# 03-ETHERNET.net
KiCad netlist of a schematic drawn in Altium Designer
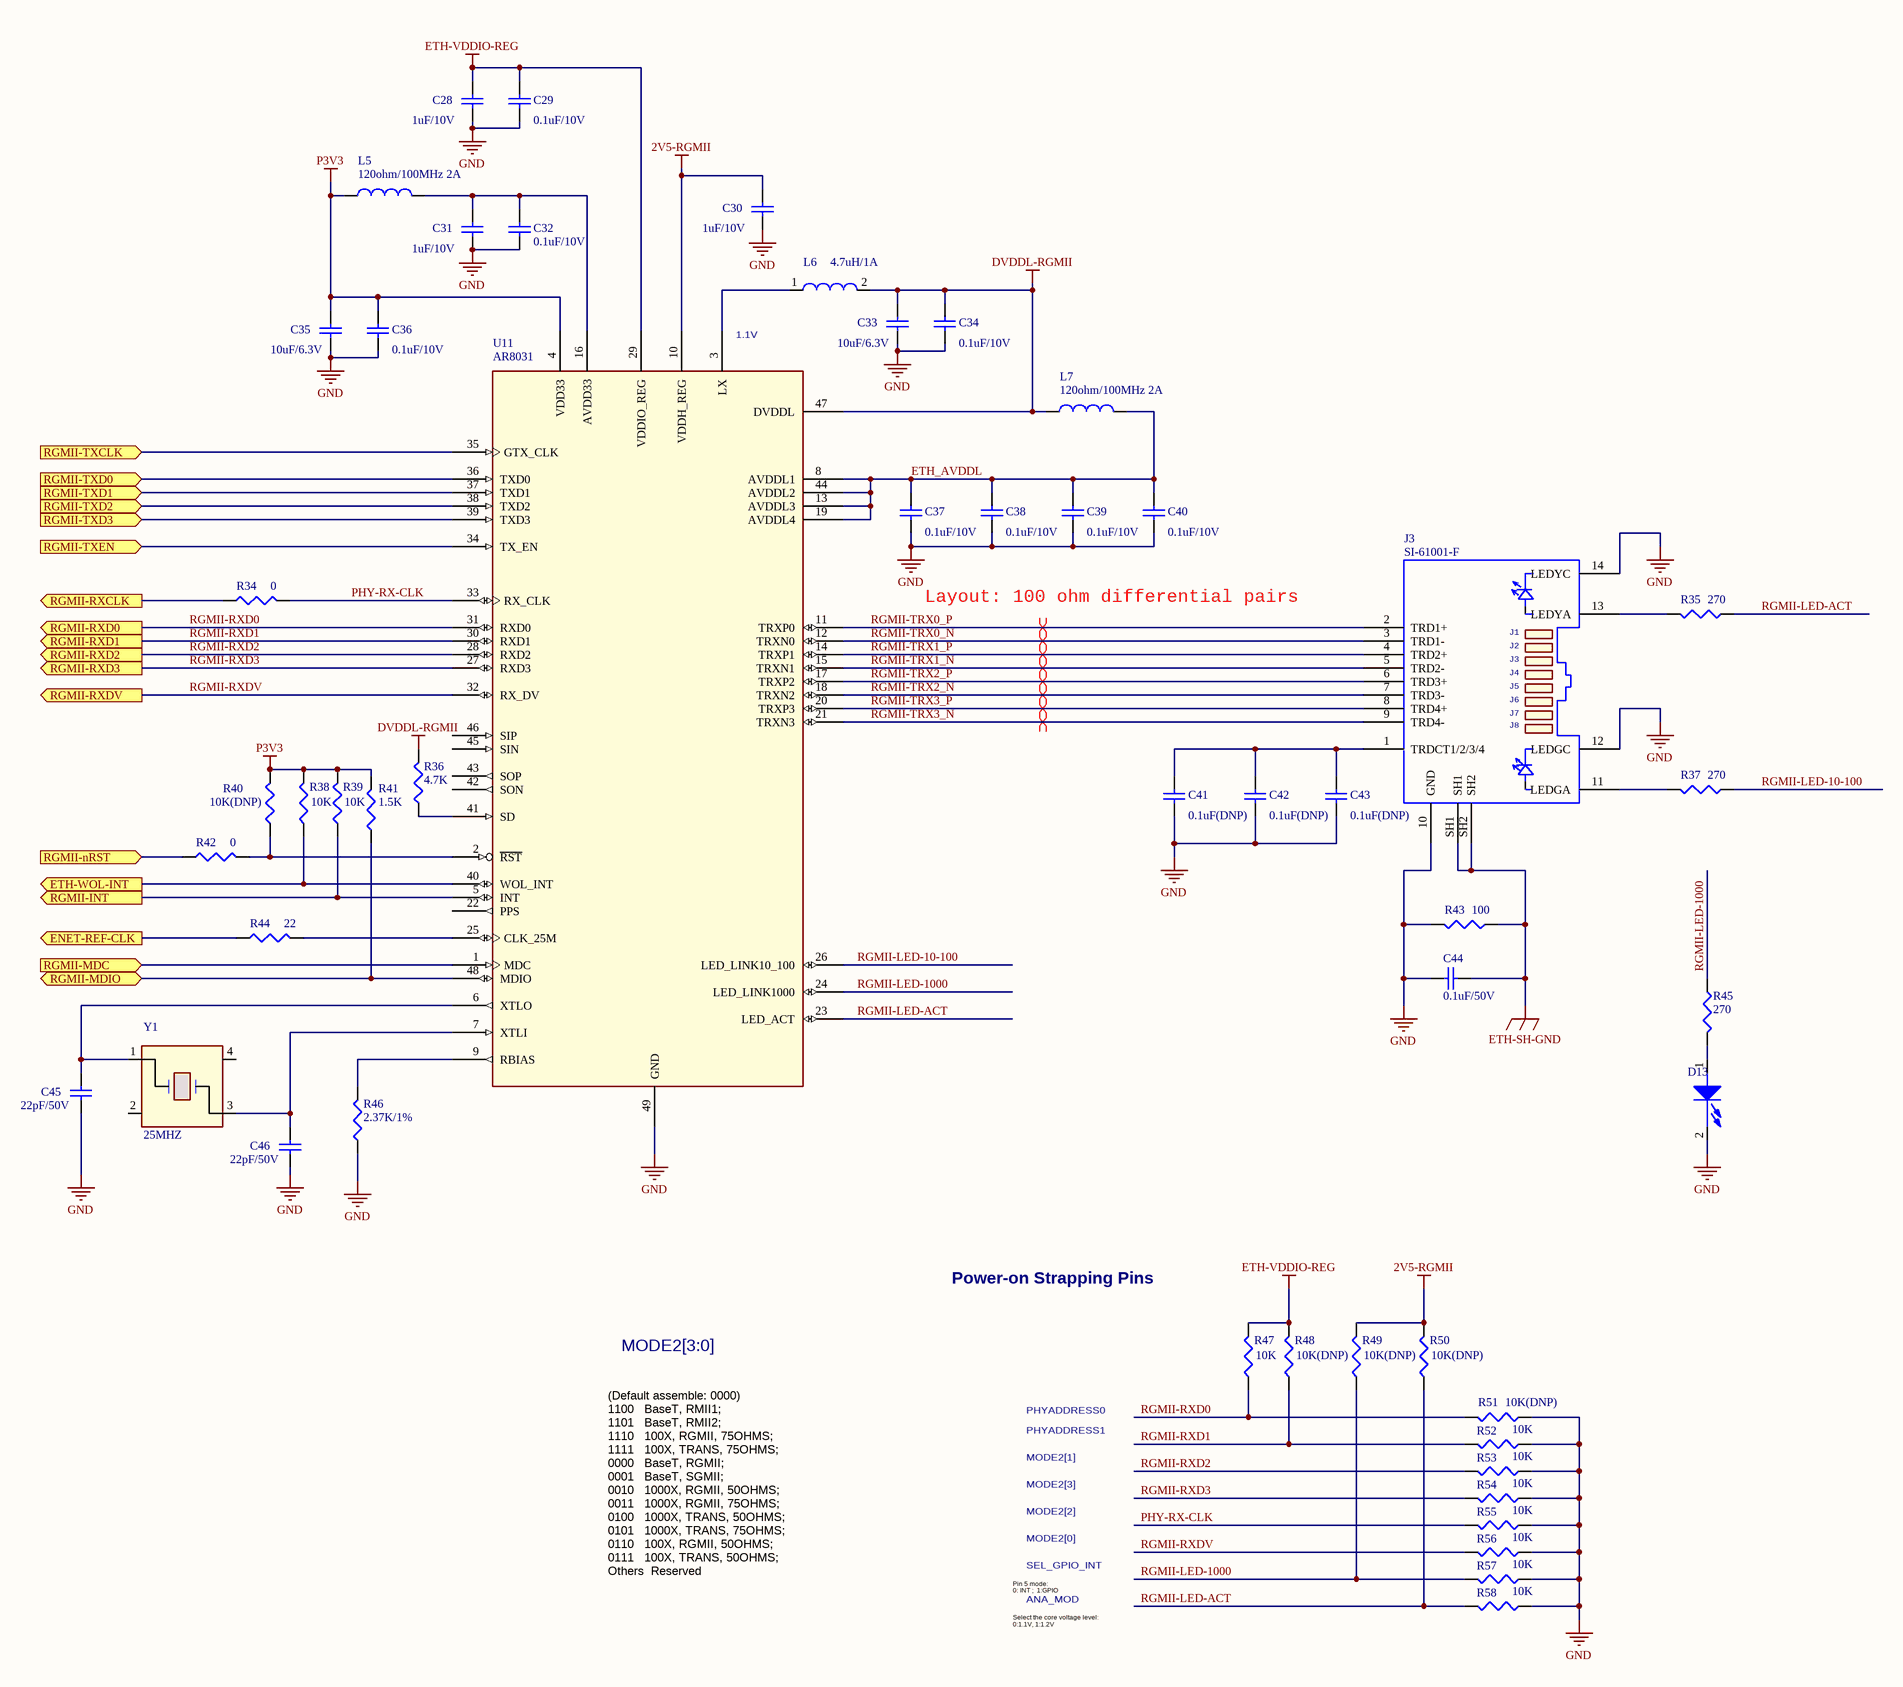
[diagram p0: 03-ETHERNET.SchDoc]

(export (version "E")
  (design (tool "Eeschema 10.0.6"))
  (components
    (comp (ref "C28")
      (value "1uF/10V")
      (footprint "0402")
      (description "Capacitor")
      (fields (field (name "PUBLISHER") "Altium Limited"))
      (libsource (lib "Miscellaneous Devices") (part "Cap"))
    )
    (comp (ref "C29")
      (value "0.1uF/10V")
      (footprint "0402")
      (description "Capacitor")
      (fields (field (name "PUBLISHER") "Altium Limited"))
      (libsource (lib "Miscellaneous Devices") (part "Cap"))
    )
    (comp (ref "C30")
      (value "1uF/10V")
      (footprint "0402")
      (description "Capacitor")
      (fields (field (name "PUBLISHER") "Altium Limited"))
      (libsource (lib "Miscellaneous Devices") (part "Cap"))
    )
    (comp (ref "C31")
      (value "1uF/10V")
      (footprint "0402")
      (description "Capacitor")
      (fields (field (name "PUBLISHER") "Altium Limited"))
      (libsource (lib "Miscellaneous Devices") (part "Cap"))
    )
    (comp (ref "C32")
      (value "0.1uF/10V")
      (footprint "0402")
      (description "Capacitor")
      (fields (field (name "PUBLISHER") "Altium Limited"))
      (libsource (lib "Miscellaneous Devices") (part "Cap"))
    )
    (comp (ref "C33")
      (value "10uF/6.3V")
      (footprint "0805")
      (description "Capacitor")
      (fields (field (name "PUBLISHER") "Altium Limited"))
      (libsource (lib "Miscellaneous Devices") (part "Cap"))
    )
    (comp (ref "C34")
      (value "0.1uF/10V")
      (footprint "0402")
      (description "Capacitor")
      (fields (field (name "PUBLISHER") "Altium Limited"))
      (libsource (lib "Miscellaneous Devices") (part "Cap"))
    )
    (comp (ref "C35")
      (value "10uF/6.3V")
      (footprint "0805")
      (description "Capacitor")
      (fields (field (name "PUBLISHER") "Altium Limited"))
      (libsource (lib "Miscellaneous Devices") (part "Cap"))
    )
    (comp (ref "C36")
      (value "0.1uF/10V")
      (footprint "0402")
      (description "Capacitor")
      (fields (field (name "PUBLISHER") "Altium Limited"))
      (libsource (lib "Miscellaneous Devices") (part "Cap"))
    )
    (comp (ref "C37")
      (value "0.1uF/10V")
      (footprint "0402")
      (description "Capacitor")
      (fields (field (name "PUBLISHER") "Altium Limited"))
      (libsource (lib "Miscellaneous Devices") (part "Cap"))
    )
    (comp (ref "C38")
      (value "0.1uF/10V")
      (footprint "0402")
      (description "Capacitor")
      (fields (field (name "PUBLISHER") "Altium Limited"))
      (libsource (lib "Miscellaneous Devices") (part "Cap"))
    )
    (comp (ref "C39")
      (value "0.1uF/10V")
      (footprint "0402")
      (description "Capacitor")
      (fields (field (name "PUBLISHER") "Altium Limited"))
      (libsource (lib "Miscellaneous Devices") (part "Cap"))
    )
    (comp (ref "C40")
      (value "0.1uF/10V")
      (footprint "0402")
      (description "Capacitor")
      (fields (field (name "PUBLISHER") "Altium Limited"))
      (libsource (lib "Miscellaneous Devices") (part "Cap"))
    )
    (comp (ref "C41")
      (value "0.1uF(DNP)")
      (footprint "0603")
      (description "Capacitor")
      (fields (field (name "PUBLISHER") "Altium Limited"))
      (libsource (lib "Miscellaneous Devices") (part "Cap"))
    )
    (comp (ref "C42")
      (value "0.1uF(DNP)")
      (footprint "0603")
      (description "Capacitor")
      (fields (field (name "PUBLISHER") "Altium Limited"))
      (libsource (lib "Miscellaneous Devices") (part "Cap"))
    )
    (comp (ref "C43")
      (value "0.1uF(DNP)")
      (footprint "0603")
      (description "Capacitor")
      (fields (field (name "PUBLISHER") "Altium Limited"))
      (libsource (lib "Miscellaneous Devices") (part "Cap"))
    )
    (comp (ref "C44")
      (value "0.1uF/50V")
      (footprint "0603")
      (description "Capacitor")
      (fields (field (name "PUBLISHER") "Altium Limited"))
      (libsource (lib "Miscellaneous Devices") (part "Cap"))
    )
    (comp (ref "C45")
      (value "22pF/50V")
      (footprint "0402")
      (description "Capacitor")
      (fields (field (name "PUBLISHER") "Altium Limited"))
      (libsource (lib "Miscellaneous Devices") (part "Cap"))
    )
    (comp (ref "C46")
      (value "22pF/50V")
      (footprint "0402")
      (description "Capacitor")
      (fields (field (name "PUBLISHER") "Altium Limited"))
      (libsource (lib "Miscellaneous Devices") (part "Cap"))
    )
    (comp (ref "D13") (value "LED GREEN") (footprint "LED0603") (libsource (lib "*") (part "LN01401_1")))
    (comp (ref "J3")
      (value "SI-61001-F")
      (footprint "SI-61001")
      (libsource (lib "Schlib") (part "SI-61001-F"))
    )
    (comp (ref "L5")
      (value "120ohm/100MHz 2A")
      (footprint "0603")
      (description "Inductor")
      (fields (field (name "PUBLISHER") "Altium Limited"))
      (libsource (lib "Miscellaneous Devices") (part "Inductor"))
    )
    (comp (ref "L6")
      (value "4.7uH/1A")
      (footprint "IND-4.7UH-1A")
      (description "IND PWR 4.7UH@1MHZ 1A 20% SMD")
      (fields (field (name "TOLERANCE") "20%"))
      (libsource (lib "*") (part "INDUCTOR"))
    )
    (comp (ref "L7")
      (value "120ohm/100MHz 2A")
      (footprint "0603")
      (description "Inductor")
      (fields (field (name "PUBLISHER") "Altium Limited"))
      (libsource (lib "Miscellaneous Devices") (part "Inductor"))
    )
    (comp (ref "R34") (value "0") (footprint "0402") (libsource (lib "*") (part "CR16-1003FM")))
    (comp (ref "R35") (value "270") (footprint "0402") (libsource (lib "*") (part "CR16-1003FM")))
    (comp (ref "R36") (value "4.7K") (footprint "0402") (libsource (lib "*") (part "CR16-1003FM")))
    (comp (ref "R37") (value "270") (footprint "0402") (libsource (lib "*") (part "CR16-1003FM")))
    (comp (ref "R38") (value "10K") (footprint "0402") (libsource (lib "*") (part "CR16-1003FM")))
    (comp (ref "R39") (value "10K") (footprint "0402") (libsource (lib "*") (part "CR16-1003FM")))
    (comp (ref "R40") (value "10K(DNP)") (footprint "0402") (libsource (lib "*") (part "CR16-1003FM")))
    (comp (ref "R41") (value "1.5K") (footprint "0402") (libsource (lib "*") (part "CR16-1003FM")))
    (comp (ref "R42") (value "0") (footprint "0402") (libsource (lib "*") (part "CR16-1003FM")))
    (comp (ref "R43") (value "100") (footprint "0402") (libsource (lib "*") (part "CR16-1003FM")))
    (comp (ref "R44") (value "22") (footprint "0402") (libsource (lib "*") (part "CR16-1003FM")))
    (comp (ref "R45") (value "270") (footprint "0402") (libsource (lib "*") (part "CR16-1003FM")))
    (comp (ref "R46") (value "2.37K/1%") (footprint "0402") (libsource (lib "*") (part "CR16-1003FM")))
    (comp (ref "R47") (value "10K") (footprint "0402") (libsource (lib "*") (part "CR16-1003FM")))
    (comp (ref "R48") (value "10K(DNP)") (footprint "0402") (libsource (lib "*") (part "CR16-1003FM")))
    (comp (ref "R49") (value "10K(DNP)") (footprint "0402") (libsource (lib "*") (part "CR16-1003FM")))
    (comp (ref "R50") (value "10K(DNP)") (footprint "0402") (libsource (lib "*") (part "CR16-1003FM")))
    (comp (ref "R51") (value "10K(DNP)") (footprint "0402") (libsource (lib "*") (part "CR16-1003FM")))
    (comp (ref "R52") (value "10K") (footprint "0402") (libsource (lib "*") (part "CR16-1003FM")))
    (comp (ref "R53") (value "10K") (footprint "0402") (libsource (lib "*") (part "CR16-1003FM")))
    (comp (ref "R54") (value "10K") (footprint "0402") (libsource (lib "*") (part "CR16-1003FM")))
    (comp (ref "R55") (value "10K") (footprint "0402") (libsource (lib "*") (part "CR16-1003FM")))
    (comp (ref "R56") (value "10K") (footprint "0402") (libsource (lib "*") (part "CR16-1003FM")))
    (comp (ref "R57") (value "10K") (footprint "0402") (libsource (lib "*") (part "CR16-1003FM")))
    (comp (ref "R58") (value "10K") (footprint "0402") (libsource (lib "*") (part "CR16-1003FM")))
    (comp (ref "U11")
      (value "AR8031")
      (footprint "QFN48")
      (description "IC XCVR ETHERNET PHY 10/100/1000G-BIT 3.3V QFN48")
      (libsource (lib "*") (part "AR8031_QFN48"))
    )
    (comp (ref "Y1")
      (value "25MHZ")
      (footprint "XTAL4_SX_3225")
      (description "XTAL 25MHZ -- -- SMT")
      (libsource (lib "*") (part "XTAL_13Y"))
    )
  )
  (nets
    (net (code "1") (name "/ENET-REF-CLK") (class "Default")
      (node (ref "R44") (pin "1") (pinfunction "1_1") (pintype "passive"))
    )
    (net (code "2") (name "/ETH-WOL-INT") (class "Default")
      (node (ref "R38") (pin "1") (pinfunction "1_1") (pintype "passive"))
      (node (ref "U11") (pin "40") (pinfunction "WOL_INT_40") (pintype "bidirectional"))
    )
    (net (code "3") (name "/ETH_AVDDL") (class "Default")
      (node (ref "C37") (pin "1") (pinfunction "1_1") (pintype "passive"))
      (node (ref "C38") (pin "1") (pinfunction "1_1") (pintype "passive"))
      (node (ref "C39") (pin "1") (pinfunction "1_1") (pintype "passive"))
      (node (ref "C40") (pin "1") (pinfunction "1_1") (pintype "passive"))
      (node (ref "L7") (pin "2") (pinfunction "2_2") (pintype "passive"))
      (node (ref "U11") (pin "13") (pinfunction "AVDDL3_13") (pintype "power_in"))
      (node (ref "U11") (pin "19") (pinfunction "AVDDL4_19") (pintype "power_in"))
      (node (ref "U11") (pin "44") (pinfunction "AVDDL2_44") (pintype "power_in"))
      (node (ref "U11") (pin "8") (pinfunction "AVDDL1_8") (pintype "power_in"))
    )
    (net (code "4") (name "/PHY-RX-CLK") (class "Default")
      (node (ref "R34") (pin "2") (pinfunction "2_2") (pintype "passive"))
      (node (ref "R55") (pin "2") (pinfunction "2_2") (pintype "passive"))
      (node (ref "U11") (pin "33") (pinfunction "RX_CLK_33") (pintype "bidirectional"))
    )
    (net (code "5") (name "/RGMII-INT") (class "Default")
      (node (ref "R39") (pin "1") (pinfunction "1_1") (pintype "passive"))
      (node (ref "U11") (pin "5") (pinfunction "INT_5") (pintype "bidirectional"))
    )
    (net (code "6") (name "/RGMII-LED-10-100") (class "Default")
      (node (ref "R37") (pin "1") (pinfunction "1_1") (pintype "passive"))
      (node (ref "U11") (pin "26") (pinfunction "LED_LINK10_100_26") (pintype "bidirectional"))
    )
    (net (code "7") (name "/RGMII-LED-1000") (class "Default")
      (node (ref "R45") (pin "1") (pinfunction "1_1") (pintype "passive"))
      (node (ref "R49") (pin "1") (pinfunction "1_1") (pintype "passive"))
      (node (ref "R57") (pin "2") (pinfunction "2_2") (pintype "passive"))
      (node (ref "U11") (pin "24") (pinfunction "LED_LINK1000_24") (pintype "bidirectional"))
    )
    (net (code "8") (name "/RGMII-LED-ACT") (class "Default")
      (node (ref "R35") (pin "1") (pinfunction "1_1") (pintype "passive"))
      (node (ref "R50") (pin "1") (pinfunction "1_1") (pintype "passive"))
      (node (ref "R58") (pin "2") (pinfunction "2_2") (pintype "passive"))
      (node (ref "U11") (pin "23") (pinfunction "LED_ACT_23") (pintype "bidirectional"))
    )
    (net (code "9") (name "/RGMII-MDC") (class "Default")
      (node (ref "U11") (pin "1") (pinfunction "MDC_1") (pintype "input"))
    )
    (net (code "10") (name "/RGMII-MDIO") (class "Default")
      (node (ref "R41") (pin "1") (pinfunction "1_1") (pintype "passive"))
      (node (ref "U11") (pin "48") (pinfunction "MDIO_48") (pintype "bidirectional"))
    )
    (net (code "11") (name "/RGMII-RXCLK") (class "Default")
      (node (ref "R34") (pin "1") (pinfunction "1_1") (pintype "passive"))
    )
    (net (code "12") (name "/RGMII-RXD0") (class "Default")
      (node (ref "R47") (pin "1") (pinfunction "1_1") (pintype "passive"))
      (node (ref "R51") (pin "2") (pinfunction "2_2") (pintype "passive"))
      (node (ref "U11") (pin "31") (pinfunction "RXD0_31") (pintype "bidirectional"))
    )
    (net (code "13") (name "/RGMII-RXD1") (class "Default")
      (node (ref "R48") (pin "1") (pinfunction "1_1") (pintype "passive"))
      (node (ref "R52") (pin "2") (pinfunction "2_2") (pintype "passive"))
      (node (ref "U11") (pin "30") (pinfunction "RXD1_30") (pintype "bidirectional"))
    )
    (net (code "14") (name "/RGMII-RXD2") (class "Default")
      (node (ref "R53") (pin "2") (pinfunction "2_2") (pintype "passive"))
      (node (ref "U11") (pin "28") (pinfunction "RXD2_28") (pintype "bidirectional"))
    )
    (net (code "15") (name "/RGMII-RXD3") (class "Default")
      (node (ref "R54") (pin "2") (pinfunction "2_2") (pintype "passive"))
      (node (ref "U11") (pin "27") (pinfunction "RXD3_27") (pintype "bidirectional"))
    )
    (net (code "16") (name "/RGMII-RXDV") (class "Default")
      (node (ref "R56") (pin "2") (pinfunction "2_2") (pintype "passive"))
      (node (ref "U11") (pin "32") (pinfunction "RX_DV_32") (pintype "bidirectional"))
    )
    (net (code "17") (name "/RGMII-TRX0_N") (class "Default")
      (node (ref "J3") (pin "3") (pinfunction "TRD1-_3") (pintype "passive"))
      (node (ref "U11") (pin "12") (pinfunction "TRXN0_12") (pintype "bidirectional"))
    )
    (net (code "18") (name "/RGMII-TRX0_P") (class "Default")
      (node (ref "J3") (pin "2") (pinfunction "TRD1+_2") (pintype "passive"))
      (node (ref "U11") (pin "11") (pinfunction "TRXP0_11") (pintype "bidirectional"))
    )
    (net (code "19") (name "/RGMII-TRX1_N") (class "Default")
      (node (ref "J3") (pin "5") (pinfunction "TRD2-_5") (pintype "passive"))
      (node (ref "U11") (pin "15") (pinfunction "TRXN1_15") (pintype "bidirectional"))
    )
    (net (code "20") (name "/RGMII-TRX1_P") (class "Default")
      (node (ref "J3") (pin "4") (pinfunction "TRD2+_4") (pintype "passive"))
      (node (ref "U11") (pin "14") (pinfunction "TRXP1_14") (pintype "bidirectional"))
    )
    (net (code "21") (name "/RGMII-TRX2_N") (class "Default")
      (node (ref "J3") (pin "7") (pinfunction "TRD3-_7") (pintype "passive"))
      (node (ref "U11") (pin "18") (pinfunction "TRXN2_18") (pintype "bidirectional"))
    )
    (net (code "22") (name "/RGMII-TRX2_P") (class "Default")
      (node (ref "J3") (pin "6") (pinfunction "TRD3+_6") (pintype "passive"))
      (node (ref "U11") (pin "17") (pinfunction "TRXP2_17") (pintype "bidirectional"))
    )
    (net (code "23") (name "/RGMII-TRX3_N") (class "Default")
      (node (ref "J3") (pin "9") (pinfunction "TRD4-_9") (pintype "passive"))
      (node (ref "U11") (pin "21") (pinfunction "TRXN3_21") (pintype "bidirectional"))
    )
    (net (code "24") (name "/RGMII-TRX3_P") (class "Default")
      (node (ref "J3") (pin "8") (pinfunction "TRD4+_8") (pintype "passive"))
      (node (ref "U11") (pin "20") (pinfunction "TRXP3_20") (pintype "bidirectional"))
    )
    (net (code "25") (name "/RGMII-TXCLK") (class "Default")
      (node (ref "U11") (pin "35") (pinfunction "GTX_CLK_35") (pintype "input"))
    )
    (net (code "26") (name "/RGMII-TXD0") (class "Default")
      (node (ref "U11") (pin "36") (pinfunction "TXD0_36") (pintype "input"))
    )
    (net (code "27") (name "/RGMII-TXD1") (class "Default")
      (node (ref "U11") (pin "37") (pinfunction "TXD1_37") (pintype "input"))
    )
    (net (code "28") (name "/RGMII-TXD2") (class "Default")
      (node (ref "U11") (pin "38") (pinfunction "TXD2_38") (pintype "input"))
    )
    (net (code "29") (name "/RGMII-TXD3") (class "Default")
      (node (ref "U11") (pin "39") (pinfunction "TXD3_39") (pintype "input"))
    )
    (net (code "30") (name "/RGMII-TXEN") (class "Default")
      (node (ref "U11") (pin "34") (pinfunction "TX_EN_34") (pintype "input"))
    )
    (net (code "31") (name "/RGMII-nRST") (class "Default")
      (node (ref "R42") (pin "1") (pinfunction "1_1") (pintype "passive"))
    )
    (net (code "32") (name "2V5-RGMII") (class "Default")
      (node (ref "C30") (pin "1") (pinfunction "1_1") (pintype "passive"))
      (node (ref "R49") (pin "2") (pinfunction "2_2") (pintype "passive"))
      (node (ref "R50") (pin "2") (pinfunction "2_2") (pintype "passive"))
      (node (ref "U11") (pin "10") (pinfunction "VDDH_REG_10") (pintype "power_in"))
    )
    (net (code "33") (name "DVDDL-RGMII") (class "Default")
      (node (ref "C33") (pin "1") (pinfunction "1_1") (pintype "passive"))
      (node (ref "C34") (pin "1") (pinfunction "1_1") (pintype "passive"))
      (node (ref "L6") (pin "2") (pinfunction "2_2") (pintype "passive"))
      (node (ref "L7") (pin "1") (pinfunction "1_1") (pintype "passive"))
      (node (ref "R36") (pin "2") (pinfunction "2_2") (pintype "passive"))
      (node (ref "U11") (pin "47") (pinfunction "DVDDL_47") (pintype "power_in"))
    )
    (net (code "34") (name "ETH-SH-GND") (class "Default")
      (node (ref "C44") (pin "2") (pinfunction "2_2") (pintype "passive"))
      (node (ref "J3") (pin "SH1") (pinfunction "SH1_SH1") (pintype "passive"))
      (node (ref "J3") (pin "SH2") (pinfunction "SH2_SH2") (pintype "passive"))
      (node (ref "R43") (pin "1") (pinfunction "1_1") (pintype "passive"))
    )
    (net (code "35") (name "ETH-VDDIO-REG") (class "Default")
      (node (ref "C28") (pin "1") (pinfunction "1_1") (pintype "passive"))
      (node (ref "C29") (pin "1") (pinfunction "1_1") (pintype "passive"))
      (node (ref "R47") (pin "2") (pinfunction "2_2") (pintype "passive"))
      (node (ref "R48") (pin "2") (pinfunction "2_2") (pintype "passive"))
      (node (ref "U11") (pin "29") (pinfunction "VDDIO_REG_29") (pintype "power_in"))
    )
    (net (code "36") (name "GND") (class "Default")
      (node (ref "C28") (pin "2") (pinfunction "2_2") (pintype "passive"))
      (node (ref "C29") (pin "2") (pinfunction "2_2") (pintype "passive"))
      (node (ref "C30") (pin "2") (pinfunction "2_2") (pintype "passive"))
      (node (ref "C31") (pin "2") (pinfunction "2_2") (pintype "passive"))
      (node (ref "C32") (pin "2") (pinfunction "2_2") (pintype "passive"))
      (node (ref "C33") (pin "2") (pinfunction "2_2") (pintype "passive"))
      (node (ref "C34") (pin "2") (pinfunction "2_2") (pintype "passive"))
      (node (ref "C35") (pin "2") (pinfunction "2_2") (pintype "passive"))
      (node (ref "C36") (pin "2") (pinfunction "2_2") (pintype "passive"))
      (node (ref "C37") (pin "2") (pinfunction "2_2") (pintype "passive"))
      (node (ref "C38") (pin "2") (pinfunction "2_2") (pintype "passive"))
      (node (ref "C39") (pin "2") (pinfunction "2_2") (pintype "passive"))
      (node (ref "C40") (pin "2") (pinfunction "2_2") (pintype "passive"))
      (node (ref "C41") (pin "2") (pinfunction "2_2") (pintype "passive"))
      (node (ref "C42") (pin "2") (pinfunction "2_2") (pintype "passive"))
      (node (ref "C43") (pin "2") (pinfunction "2_2") (pintype "passive"))
      (node (ref "C44") (pin "1") (pinfunction "1_1") (pintype "passive"))
      (node (ref "C45") (pin "2") (pinfunction "2_2") (pintype "passive"))
      (node (ref "C46") (pin "2") (pinfunction "2_2") (pintype "passive"))
      (node (ref "D13") (pin "2") (pinfunction "CATHODE_2") (pintype "passive"))
      (node (ref "J3") (pin "10") (pinfunction "GND_10") (pintype "power_in"))
      (node (ref "J3") (pin "12") (pinfunction "LEDGC_12") (pintype "passive"))
      (node (ref "J3") (pin "14") (pinfunction "LEDYC_14") (pintype "passive"))
      (node (ref "R43") (pin "2") (pinfunction "2_2") (pintype "passive"))
      (node (ref "R46") (pin "1") (pinfunction "1_1") (pintype "passive"))
      (node (ref "R51") (pin "1") (pinfunction "1_1") (pintype "passive"))
      (node (ref "R52") (pin "1") (pinfunction "1_1") (pintype "passive"))
      (node (ref "R53") (pin "1") (pinfunction "1_1") (pintype "passive"))
      (node (ref "R54") (pin "1") (pinfunction "1_1") (pintype "passive"))
      (node (ref "R55") (pin "1") (pinfunction "1_1") (pintype "passive"))
      (node (ref "R56") (pin "1") (pinfunction "1_1") (pintype "passive"))
      (node (ref "R57") (pin "1") (pinfunction "1_1") (pintype "passive"))
      (node (ref "R58") (pin "1") (pinfunction "1_1") (pintype "passive"))
      (node (ref "U11") (pin "49") (pinfunction "GND_49") (pintype "power_in"))
    )
    (net (code "37") (name "Net-(D13-ANODE)") (class "Default")
      (node (ref "D13") (pin "1") (pinfunction "ANODE_1") (pintype "passive"))
      (node (ref "R45") (pin "2") (pinfunction "2_2") (pintype "passive"))
    )
    (net (code "38") (name "Net-(J3-LEDGA)") (class "Default")
      (node (ref "J3") (pin "11") (pinfunction "LEDGA_11") (pintype "passive"))
      (node (ref "R37") (pin "2") (pinfunction "2_2") (pintype "passive"))
    )
    (net (code "39") (name "Net-(J3-LEDYA)") (class "Default")
      (node (ref "J3") (pin "13") (pinfunction "LEDYA_13") (pintype "passive"))
      (node (ref "R35") (pin "2") (pinfunction "2_2") (pintype "passive"))
    )
    (net (code "40") (name "Net-(J3-TRDCT1{slash}2{slash}3{slash}4)") (class "Default")
      (node (ref "C41") (pin "1") (pinfunction "1_1") (pintype "passive"))
      (node (ref "C42") (pin "1") (pinfunction "1_1") (pintype "passive"))
      (node (ref "C43") (pin "1") (pinfunction "1_1") (pintype "passive"))
      (node (ref "J3") (pin "1") (pinfunction "TRDCT1/2/3/4_1") (pintype "passive"))
    )
    (net (code "41") (name "Net-(U11-AVDD33)") (class "Default")
      (node (ref "C31") (pin "1") (pinfunction "1_1") (pintype "passive"))
      (node (ref "C32") (pin "1") (pinfunction "1_1") (pintype "passive"))
      (node (ref "L5") (pin "2") (pinfunction "2_2") (pintype "passive"))
      (node (ref "U11") (pin "16") (pinfunction "AVDD33_16") (pintype "power_in"))
    )
    (net (code "42") (name "Net-(U11-CLK_25M)") (class "Default")
      (node (ref "R44") (pin "2") (pinfunction "2_2") (pintype "passive"))
      (node (ref "U11") (pin "25") (pinfunction "CLK_25M_25") (pintype "bidirectional"))
    )
    (net (code "43") (name "Net-(U11-LX)") (class "Default")
      (node (ref "L6") (pin "1") (pinfunction "1_1") (pintype "passive"))
      (node (ref "U11") (pin "3") (pinfunction "LX_3") (pintype "power_in"))
    )
    (net (code "44") (name "Net-(U11-RBIAS)") (class "Default")
      (node (ref "R46") (pin "2") (pinfunction "2_2") (pintype "passive"))
      (node (ref "U11") (pin "9") (pinfunction "RBIAS_9") (pintype "output"))
    )
    (net (code "45") (name "Net-(U11-SD)") (class "Default")
      (node (ref "R36") (pin "1") (pinfunction "1_1") (pintype "passive"))
      (node (ref "U11") (pin "41") (pinfunction "SD_41") (pintype "input"))
    )
    (net (code "46") (name "Net-(U11-XTLI)") (class "Default")
      (node (ref "C46") (pin "1") (pinfunction "1_1") (pintype "passive"))
      (node (ref "U11") (pin "7") (pinfunction "XTLI_7") (pintype "input"))
      (node (ref "Y1") (pin "3") (pinfunction "3_3") (pintype "passive"))
    )
    (net (code "47") (name "Net-(U11-XTLO)") (class "Default")
      (node (ref "C45") (pin "1") (pinfunction "1_1") (pintype "passive"))
      (node (ref "U11") (pin "6") (pinfunction "XTLO_6") (pintype "output"))
      (node (ref "Y1") (pin "1") (pinfunction "1_1") (pintype "passive"))
    )
    (net (code "48") (name "Net-(U11-~{RST})") (class "Default")
      (node (ref "R40") (pin "1") (pinfunction "1_1") (pintype "passive"))
      (node (ref "R42") (pin "2") (pinfunction "2_2") (pintype "passive"))
      (node (ref "U11") (pin "2") (pinfunction "~{RST}_2") (pintype "input"))
    )
    (net (code "49") (name "P3V3") (class "Default")
      (node (ref "C35") (pin "1") (pinfunction "1_1") (pintype "passive"))
      (node (ref "C36") (pin "1") (pinfunction "1_1") (pintype "passive"))
      (node (ref "L5") (pin "1") (pinfunction "1_1") (pintype "passive"))
      (node (ref "R38") (pin "2") (pinfunction "2_2") (pintype "passive"))
      (node (ref "R39") (pin "2") (pinfunction "2_2") (pintype "passive"))
      (node (ref "R40") (pin "2") (pinfunction "2_2") (pintype "passive"))
      (node (ref "R41") (pin "2") (pinfunction "2_2") (pintype "passive"))
      (node (ref "U11") (pin "4") (pinfunction "VDD33_4") (pintype "power_in"))
    )
    (net (code "50") (name "unconnected-(U11-PPS-Pad22)") (class "Default")
      (node (ref "U11") (pin "22") (pinfunction "PPS_22") (pintype "output"))
    )
    (net (code "51") (name "unconnected-(U11-SIN-Pad45)") (class "Default")
      (node (ref "U11") (pin "45") (pinfunction "SIN_45") (pintype "input"))
    )
    (net (code "52") (name "unconnected-(U11-SIP-Pad46)") (class "Default")
      (node (ref "U11") (pin "46") (pinfunction "SIP_46") (pintype "input"))
    )
    (net (code "53") (name "unconnected-(U11-SON-Pad42)") (class "Default")
      (node (ref "U11") (pin "42") (pinfunction "SON_42") (pintype "output"))
    )
    (net (code "54") (name "unconnected-(U11-SOP-Pad43)") (class "Default")
      (node (ref "U11") (pin "43") (pinfunction "SOP_43") (pintype "output"))
    )
    (net (code "55") (name "unconnected-(Y1-Pad2)") (class "Default")
      (node (ref "Y1") (pin "2") (pinfunction "2_2") (pintype "passive"))
    )
    (net (code "56") (name "unconnected-(Y1-Pad4)") (class "Default")
      (node (ref "Y1") (pin "4") (pinfunction "4_4") (pintype "passive"))
    )
  )
)
